# aquarium.net
KiCad netlist of a schematic drawn in EAGLE
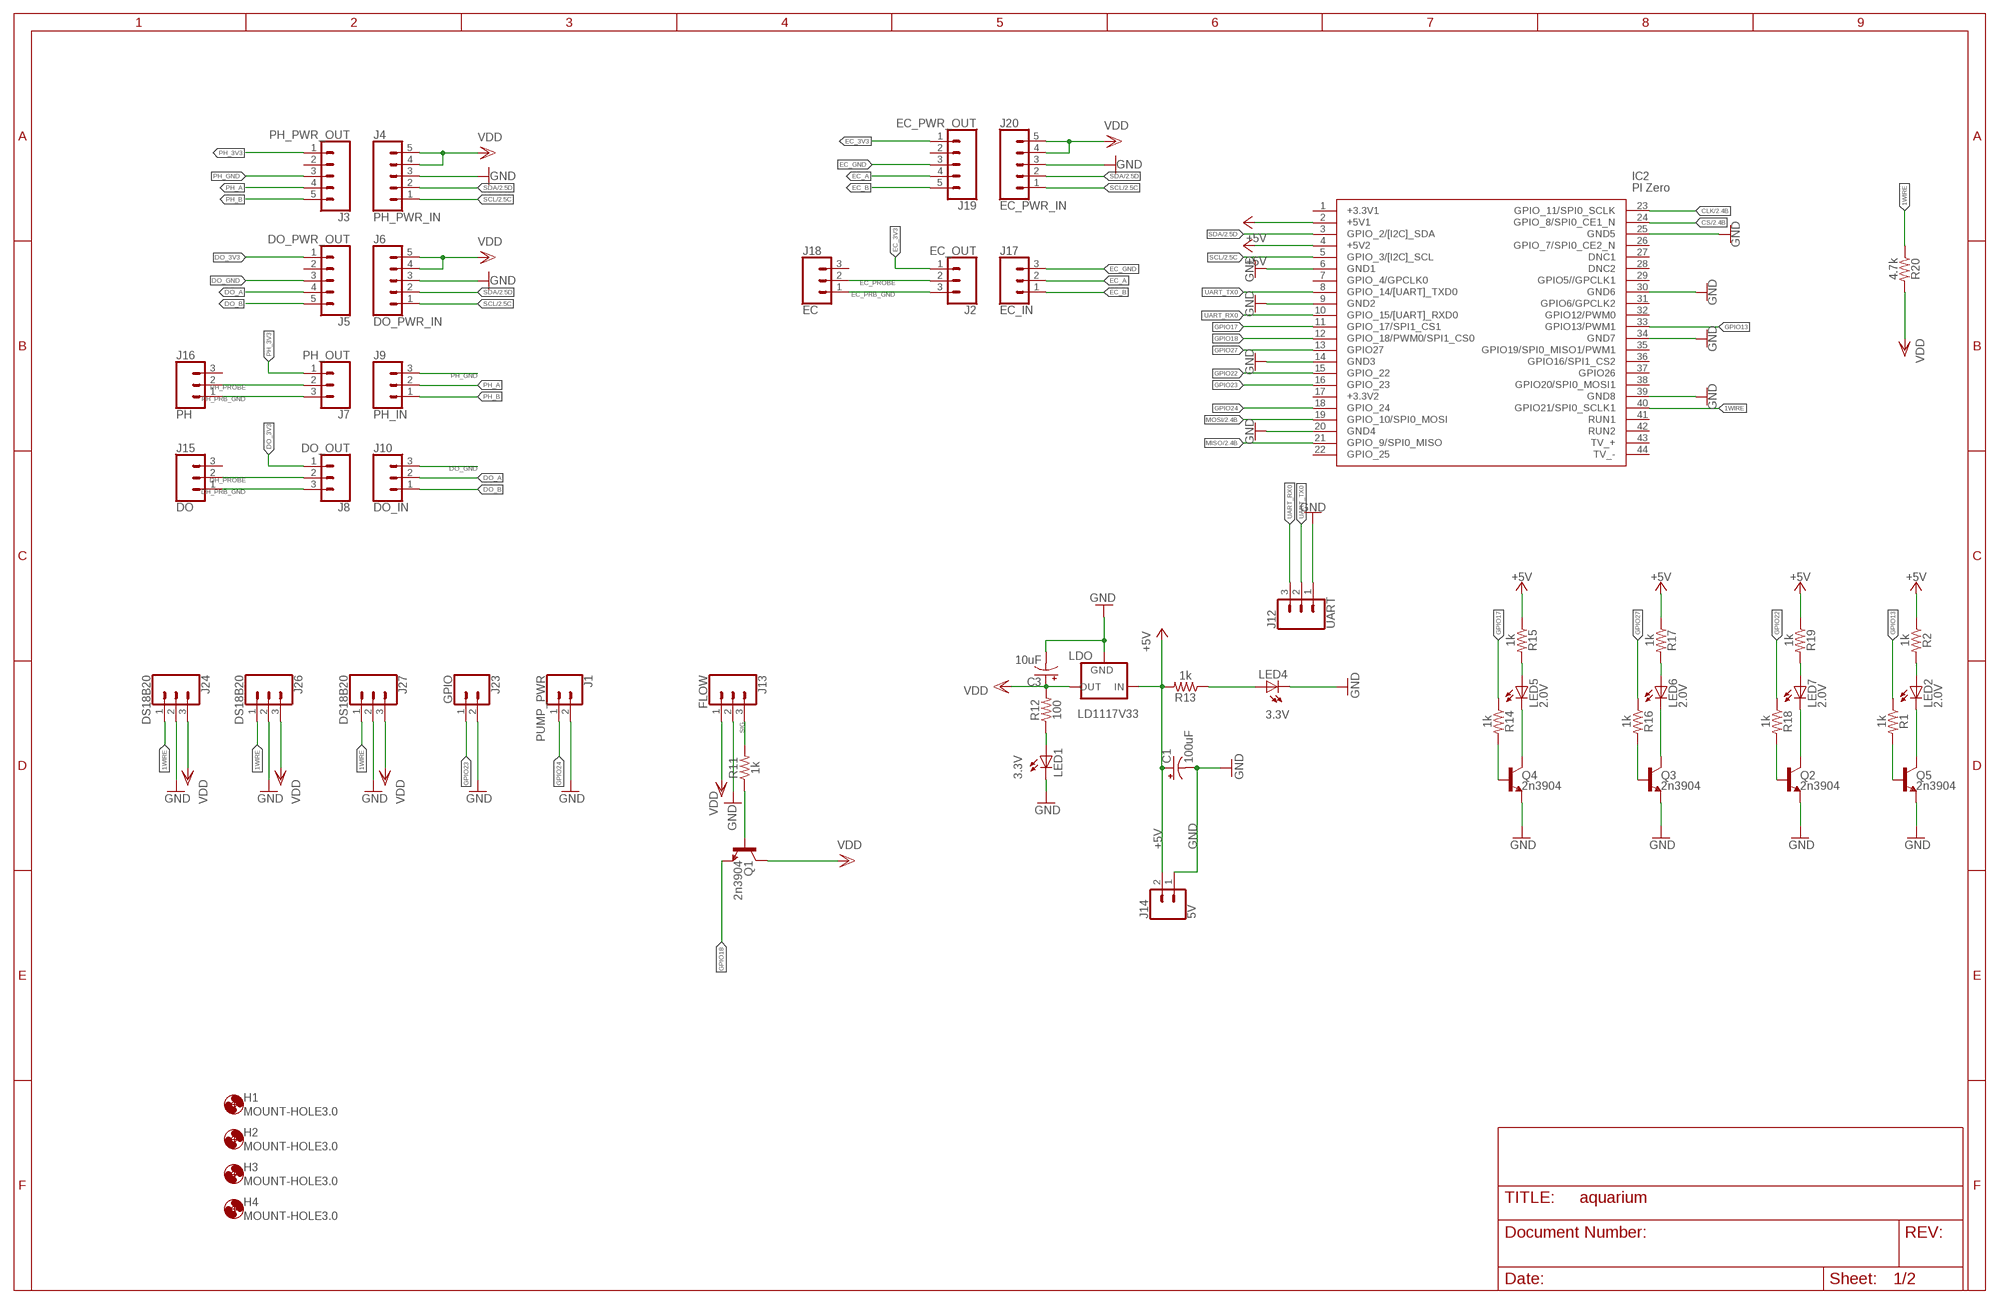
[diagram p0: schematic, sheet 1]
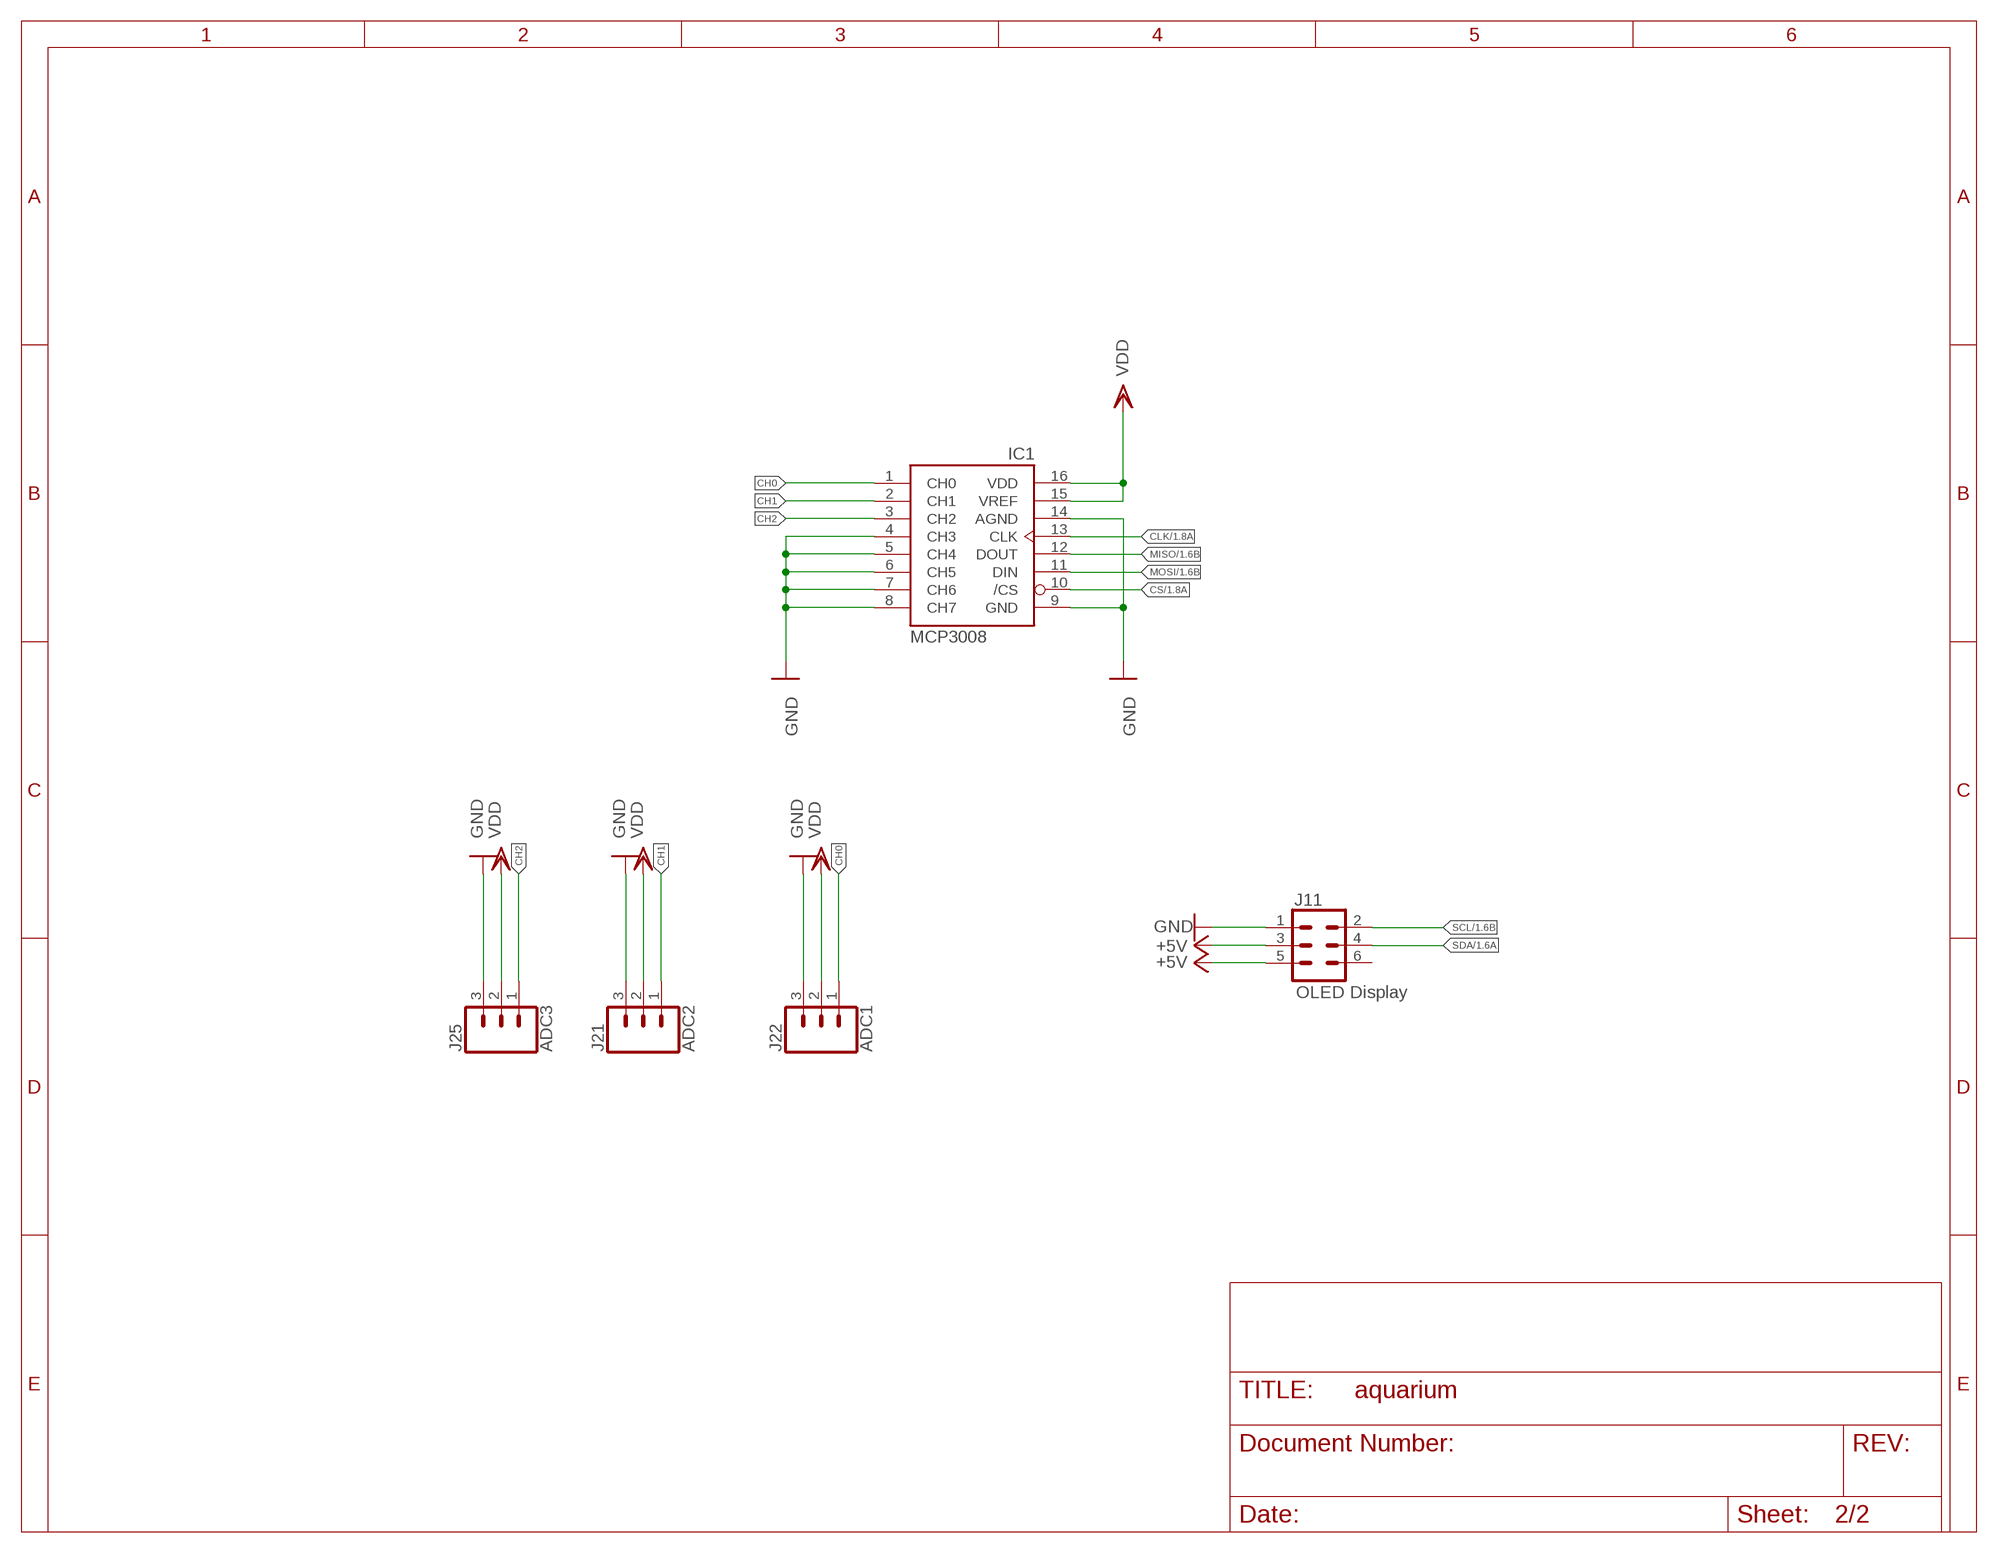
[diagram p1: schematic, sheet 2]

(export (version "E")
  (design (tool "Eeschema 10.0.6"))
  (components
    (comp (ref "C1")
      (value "100uF")
      (footprint "eagle-import:CPOL-RADIAL-2.5MM-6.5MM")
      (libsource (lib "eagle-import") (part "100UF-POLAR-RADIAL-2.5MM-25V-20%"))
    )
    (comp (ref "C3")
      (value "10uF")
      (footprint "eagle-import:CPOL-RADIAL-2.5MM-5MM")
      (libsource (lib "eagle-import") (part "10UF-POLAR-RADIAL-2.5MM-25V-20%"))
    )
    (comp (ref "H1")
      (value "MOUNT-HOLE3.0")
      (footprint "eagle-import:3,0")
      (libsource (lib "eagle-import") (part "MOUNT-HOLE3.0"))
    )
    (comp (ref "H2")
      (value "MOUNT-HOLE3.0")
      (footprint "eagle-import:3,0")
      (libsource (lib "eagle-import") (part "MOUNT-HOLE3.0"))
    )
    (comp (ref "H3")
      (value "MOUNT-HOLE3.0")
      (footprint "eagle-import:3,0")
      (libsource (lib "eagle-import") (part "MOUNT-HOLE3.0"))
    )
    (comp (ref "H4")
      (value "MOUNT-HOLE3.0")
      (footprint "eagle-import:3,0")
      (libsource (lib "eagle-import") (part "MOUNT-HOLE3.0"))
    )
    (comp (ref "IC2")
      (value "PI Zero")
      (footprint "eagle-import:RASPBERRYPIZEROWV13")
      (fields (field (name "ARROW_PART_NUMBER") "Raspberry Pi Zero W (v1.3)"))
      (libsource (lib "eagle-import") (part "RASPBERRY_PI_ZERO_W_(V1.3)"))
    )
    (comp (ref "J1")
      (value "PUMP_PWR")
      (footprint "eagle-import:1X02")
      (libsource (lib "eagle-import") (part "CONN_02"))
    )
    (comp (ref "J2")
      (value "EC_OUT")
      (footprint "eagle-import:1X03")
      (libsource (lib "eagle-import") (part "CONN_03"))
    )
    (comp (ref "J3")
      (value "PH_PWR_OUT")
      (footprint "eagle-import:1X05")
      (libsource (lib "eagle-import") (part "CONN_05"))
    )
    (comp (ref "J4")
      (value "PH_PWR_IN")
      (footprint "eagle-import:1X05")
      (libsource (lib "eagle-import") (part "CONN_05"))
    )
    (comp (ref "J5")
      (value "DO_PWR_OUT")
      (footprint "eagle-import:1X05")
      (libsource (lib "eagle-import") (part "CONN_05"))
    )
    (comp (ref "J6")
      (value "DO_PWR_IN")
      (footprint "eagle-import:1X05")
      (libsource (lib "eagle-import") (part "CONN_05"))
    )
    (comp (ref "J7")
      (value "PH_OUT")
      (footprint "eagle-import:1X03")
      (libsource (lib "eagle-import") (part "CONN_03"))
    )
    (comp (ref "J8")
      (value "DO_OUT")
      (footprint "eagle-import:1X03")
      (libsource (lib "eagle-import") (part "CONN_03"))
    )
    (comp (ref "J9")
      (value "PH_IN")
      (footprint "eagle-import:1X03")
      (libsource (lib "eagle-import") (part "CONN_03"))
    )
    (comp (ref "J10")
      (value "DO_IN")
      (footprint "eagle-import:1X03")
      (libsource (lib "eagle-import") (part "CONN_03"))
    )
    (comp (ref "J12")
      (value "UART")
      (footprint "eagle-import:1X03")
      (libsource (lib "eagle-import") (part "CONN_03"))
    )
    (comp (ref "J13")
      (value "FLOW")
      (footprint "eagle-import:1X03")
      (libsource (lib "eagle-import") (part "CONN_03"))
    )
    (comp (ref "J14")
      (value "5V")
      (footprint "eagle-import:1X02")
      (libsource (lib "eagle-import") (part "CONN_02"))
    )
    (comp (ref "J15")
      (value "DO")
      (footprint "eagle-import:1X03")
      (libsource (lib "eagle-import") (part "CONN_03"))
    )
    (comp (ref "J16")
      (value "PH")
      (footprint "eagle-import:1X03")
      (libsource (lib "eagle-import") (part "CONN_03"))
    )
    (comp (ref "J17")
      (value "EC_IN")
      (footprint "eagle-import:1X03")
      (libsource (lib "eagle-import") (part "CONN_03"))
    )
    (comp (ref "J18")
      (value "EC")
      (footprint "eagle-import:1X03")
      (libsource (lib "eagle-import") (part "CONN_03"))
    )
    (comp (ref "J19")
      (value "EC_PWR_OUT")
      (footprint "eagle-import:1X05")
      (libsource (lib "eagle-import") (part "CONN_05"))
    )
    (comp (ref "J20")
      (value "EC_PWR_IN")
      (footprint "eagle-import:1X05")
      (libsource (lib "eagle-import") (part "CONN_05"))
    )
    (comp (ref "J23")
      (value "GPIO")
      (footprint "eagle-import:1X02")
      (libsource (lib "eagle-import") (part "CONN_02"))
    )
    (comp (ref "J24")
      (value "DS18B20")
      (footprint "eagle-import:1X03")
      (libsource (lib "eagle-import") (part "CONN_03"))
    )
    (comp (ref "J26")
      (value "DS18B20")
      (footprint "eagle-import:1X03")
      (libsource (lib "eagle-import") (part "CONN_03"))
    )
    (comp (ref "J27")
      (value "DS18B20")
      (footprint "eagle-import:1X03")
      (libsource (lib "eagle-import") (part "CONN_03"))
    )
    (comp (ref "LDO")
      (value "LD1117V33")
      (footprint "eagle-import:78XXL")
      (libsource (lib "eagle-import") (part "V_REG_LD1117VXX"))
    )
    (comp (ref "LED1")
      (value "3.3V")
      (footprint "eagle-import:LED3MM")
      (libsource (lib "eagle-import") (part "LED3MM"))
    )
    (comp (ref "LED2")
      (value "2.0V")
      (footprint "eagle-import:LED3MM")
      (libsource (lib "eagle-import") (part "LED3MM"))
    )
    (comp (ref "LED4")
      (value "3.3V")
      (footprint "eagle-import:LED3MM")
      (libsource (lib "eagle-import") (part "LED3MM"))
    )
    (comp (ref "LED5")
      (value "2.0V")
      (footprint "eagle-import:LED3MM")
      (libsource (lib "eagle-import") (part "LED3MM"))
    )
    (comp (ref "LED6")
      (value "2.0V")
      (footprint "eagle-import:LED3MM")
      (libsource (lib "eagle-import") (part "LED3MM"))
    )
    (comp (ref "LED7")
      (value "2.0V")
      (footprint "eagle-import:LED3MM")
      (libsource (lib "eagle-import") (part "LED3MM"))
    )
    (comp (ref "Q1")
      (value "2n3904")
      (footprint "eagle-import:TO-92")
      (libsource (lib "eagle-import") (part "TRANS_NPN-2N3904"))
    )
    (comp (ref "Q2")
      (value "2n3904")
      (footprint "eagle-import:TO-92")
      (libsource (lib "eagle-import") (part "TRANS_NPN-2N3904"))
    )
    (comp (ref "Q3")
      (value "2n3904")
      (footprint "eagle-import:TO-92")
      (libsource (lib "eagle-import") (part "TRANS_NPN-2N3904"))
    )
    (comp (ref "Q4")
      (value "2n3904")
      (footprint "eagle-import:TO-92")
      (libsource (lib "eagle-import") (part "TRANS_NPN-2N3904"))
    )
    (comp (ref "Q5")
      (value "2n3904")
      (footprint "eagle-import:TO-92")
      (libsource (lib "eagle-import") (part "TRANS_NPN-2N3904"))
    )
    (comp (ref "R1")
      (value "1k")
      (footprint "eagle-import:AXIAL-0.3")
      (libsource (lib "eagle-import") (part "1KOHM-HORIZ-1/4W-5%"))
    )
    (comp (ref "R2")
      (value "1k")
      (footprint "eagle-import:AXIAL-0.3")
      (libsource (lib "eagle-import") (part "1KOHM-HORIZ-1/4W-5%"))
    )
    (comp (ref "R11")
      (value "1k")
      (footprint "eagle-import:AXIAL-0.3")
      (libsource (lib "eagle-import") (part "1KOHM-HORIZ-1/4W-5%"))
    )
    (comp (ref "R12")
      (value "100")
      (footprint "eagle-import:AXIAL-0.3")
      (libsource (lib "eagle-import") (part "1KOHM-HORIZ-1/4W-5%"))
    )
    (comp (ref "R13")
      (value "1k")
      (footprint "eagle-import:AXIAL-0.3")
      (libsource (lib "eagle-import") (part "1KOHM-HORIZ-1/4W-5%"))
    )
    (comp (ref "R14")
      (value "1k")
      (footprint "eagle-import:AXIAL-0.3")
      (libsource (lib "eagle-import") (part "1KOHM-HORIZ-1/4W-5%"))
    )
    (comp (ref "R15")
      (value "1k")
      (footprint "eagle-import:AXIAL-0.3")
      (libsource (lib "eagle-import") (part "1KOHM-HORIZ-1/4W-5%"))
    )
    (comp (ref "R16")
      (value "1k")
      (footprint "eagle-import:AXIAL-0.3")
      (libsource (lib "eagle-import") (part "1KOHM-HORIZ-1/4W-5%"))
    )
    (comp (ref "R17")
      (value "1k")
      (footprint "eagle-import:AXIAL-0.3")
      (libsource (lib "eagle-import") (part "1KOHM-HORIZ-1/4W-5%"))
    )
    (comp (ref "R18")
      (value "1k")
      (footprint "eagle-import:AXIAL-0.3")
      (libsource (lib "eagle-import") (part "1KOHM-HORIZ-1/4W-5%"))
    )
    (comp (ref "R19")
      (value "1k")
      (footprint "eagle-import:AXIAL-0.3")
      (libsource (lib "eagle-import") (part "1KOHM-HORIZ-1/4W-5%"))
    )
    (comp (ref "R20")
      (value "4.7k")
      (footprint "eagle-import:AXIAL-0.3")
      (libsource (lib "eagle-import") (part "1KOHM-HORIZ-1/4W-5%"))
    )
    (comp (ref "IC1")
      (value "MCP3008")
      (footprint "eagle-import:DIL16")
      (libsource (lib "eagle-import") (part "MCP3008"))
    )
    (comp (ref "J11")
      (value "OLED Display")
      (footprint "eagle-import:2X3")
      (libsource (lib "eagle-import") (part "CONN_03X2FEMALE"))
    )
    (comp (ref "J21")
      (value "ADC2")
      (footprint "eagle-import:1X03")
      (libsource (lib "eagle-import") (part "CONN_03"))
    )
    (comp (ref "J22")
      (value "ADC1")
      (footprint "eagle-import:1X03")
      (libsource (lib "eagle-import") (part "CONN_03"))
    )
    (comp (ref "J25")
      (value "ADC3")
      (footprint "eagle-import:1X03")
      (libsource (lib "eagle-import") (part "CONN_03"))
    )
  )
  (nets
    (net (code "1") (name "+5V") (class "Default")
      (node (ref "C1") (pin "1") (pinfunction "+_1") (pintype "passive"))
      (node (ref "IC2") (pin "2") (pinfunction "+5V1_2") (pintype "bidirectional"))
      (node (ref "IC2") (pin "4") (pinfunction "+5V2_4") (pintype "bidirectional"))
      (node (ref "J11") (pin "3") (pinfunction "3_3") (pintype "bidirectional"))
      (node (ref "J11") (pin "5") (pinfunction "5_5") (pintype "bidirectional"))
      (node (ref "J14") (pin "2") (pinfunction "2_2") (pintype "passive"))
      (node (ref "LDO") (pin "OUT") (pinfunction "IN_OUT") (pintype "input"))
      (node (ref "R13") (pin "P$2") (pinfunction "2_P$2") (pintype "passive"))
      (node (ref "R15") (pin "P$1") (pinfunction "1_P$1") (pintype "passive"))
      (node (ref "R17") (pin "P$1") (pinfunction "1_P$1") (pintype "passive"))
      (node (ref "R19") (pin "P$1") (pinfunction "1_P$1") (pintype "passive"))
      (node (ref "R2") (pin "P$1") (pinfunction "1_P$1") (pintype "passive"))
    )
    (net (code "2") (name "1WIRE") (class "Default")
      (node (ref "IC2") (pin "40") (pinfunction "GPIO21/SPI0_SCLK1_40") (pintype "bidirectional"))
      (node (ref "J24") (pin "1") (pinfunction "1_1") (pintype "passive"))
      (node (ref "J26") (pin "1") (pinfunction "1_1") (pintype "passive"))
      (node (ref "J27") (pin "1") (pinfunction "1_1") (pintype "passive"))
      (node (ref "R20") (pin "P$1") (pinfunction "1_P$1") (pintype "passive"))
    )
    (net (code "3") (name "CH0") (class "Default")
      (node (ref "IC1") (pin "1") (pinfunction "CH0_1") (pintype "input"))
      (node (ref "J22") (pin "1") (pinfunction "1_1") (pintype "passive"))
    )
    (net (code "4") (name "CH1") (class "Default")
      (node (ref "IC1") (pin "2") (pinfunction "CH1_2") (pintype "input"))
      (node (ref "J21") (pin "1") (pinfunction "1_1") (pintype "passive"))
    )
    (net (code "5") (name "CH2") (class "Default")
      (node (ref "IC1") (pin "3") (pinfunction "CH2_3") (pintype "input"))
      (node (ref "J25") (pin "1") (pinfunction "1_1") (pintype "passive"))
    )
    (net (code "6") (name "CLK") (class "Default")
      (node (ref "IC1") (pin "13") (pinfunction "CLK_13") (pintype "input"))
      (node (ref "IC2") (pin "23") (pinfunction "GPIO_11/SPI0_SCLK_23") (pintype "bidirectional"))
    )
    (net (code "7") (name "CS") (class "Default")
      (node (ref "IC1") (pin "10") (pinfunction "/CS_10") (pintype "input"))
      (node (ref "IC2") (pin "24") (pinfunction "GPIO_8/SPI0_CE1_N_24") (pintype "bidirectional"))
    )
    (net (code "8") (name "DH_PRB_GND") (class "Default")
      (node (ref "J15") (pin "1") (pinfunction "1_1") (pintype "passive"))
      (node (ref "J8") (pin "3") (pinfunction "3_3") (pintype "passive"))
    )
    (net (code "9") (name "DH_PROBE") (class "Default")
      (node (ref "J15") (pin "2") (pinfunction "2_2") (pintype "passive"))
      (node (ref "J8") (pin "2") (pinfunction "2_2") (pintype "passive"))
    )
    (net (code "10") (name "DO_3V3") (class "Default")
      (node (ref "J5") (pin "1") (pinfunction "1_1") (pintype "passive"))
      (node (ref "J8") (pin "1") (pinfunction "1_1") (pintype "passive"))
    )
    (net (code "11") (name "DO_A") (class "Default")
      (node (ref "J10") (pin "2") (pinfunction "2_2") (pintype "passive"))
      (node (ref "J5") (pin "4") (pinfunction "4_4") (pintype "passive"))
    )
    (net (code "12") (name "DO_B") (class "Default")
      (node (ref "J10") (pin "1") (pinfunction "1_1") (pintype "passive"))
      (node (ref "J5") (pin "5") (pinfunction "5_5") (pintype "passive"))
    )
    (net (code "13") (name "DO_GND") (class "Default")
      (node (ref "J10") (pin "3") (pinfunction "3_3") (pintype "passive"))
      (node (ref "J5") (pin "3") (pinfunction "3_3") (pintype "passive"))
    )
    (net (code "14") (name "EC_3V3") (class "Default")
      (node (ref "J19") (pin "1") (pinfunction "1_1") (pintype "passive"))
      (node (ref "J2") (pin "1") (pinfunction "1_1") (pintype "passive"))
    )
    (net (code "15") (name "EC_A") (class "Default")
      (node (ref "J17") (pin "2") (pinfunction "2_2") (pintype "passive"))
      (node (ref "J19") (pin "4") (pinfunction "4_4") (pintype "passive"))
    )
    (net (code "16") (name "EC_B") (class "Default")
      (node (ref "J17") (pin "1") (pinfunction "1_1") (pintype "passive"))
      (node (ref "J19") (pin "5") (pinfunction "5_5") (pintype "passive"))
    )
    (net (code "17") (name "EC_GND") (class "Default")
      (node (ref "J17") (pin "3") (pinfunction "3_3") (pintype "passive"))
      (node (ref "J19") (pin "3") (pinfunction "3_3") (pintype "passive"))
    )
    (net (code "18") (name "EC_PRB_GND") (class "Default")
      (node (ref "J18") (pin "1") (pinfunction "1_1") (pintype "passive"))
      (node (ref "J2") (pin "3") (pinfunction "3_3") (pintype "passive"))
    )
    (net (code "19") (name "EC_PROBE") (class "Default")
      (node (ref "J18") (pin "2") (pinfunction "2_2") (pintype "passive"))
      (node (ref "J2") (pin "2") (pinfunction "2_2") (pintype "passive"))
    )
    (net (code "20") (name "GND") (class "Default")
      (node (ref "C1") (pin "2") (pinfunction "-_2") (pintype "passive"))
      (node (ref "C3") (pin "2") (pinfunction "-_2") (pintype "passive"))
      (node (ref "IC1") (pin "14") (pinfunction "AGND_14") (pintype "power_in"))
      (node (ref "IC1") (pin "4") (pinfunction "CH3_4") (pintype "input"))
      (node (ref "IC1") (pin "5") (pinfunction "CH4_5") (pintype "input"))
      (node (ref "IC1") (pin "6") (pinfunction "CH5_6") (pintype "input"))
      (node (ref "IC1") (pin "7") (pinfunction "CH6_7") (pintype "input"))
      (node (ref "IC1") (pin "8") (pinfunction "CH7_8") (pintype "input"))
      (node (ref "IC1") (pin "9") (pinfunction "GND_9") (pintype "power_in"))
      (node (ref "IC2") (pin "14") (pinfunction "GND3_14") (pintype "bidirectional"))
      (node (ref "IC2") (pin "20") (pinfunction "GND4_20") (pintype "bidirectional"))
      (node (ref "IC2") (pin "25") (pinfunction "GND5_25") (pintype "bidirectional"))
      (node (ref "IC2") (pin "30") (pinfunction "GND6_30") (pintype "bidirectional"))
      (node (ref "IC2") (pin "34") (pinfunction "GND7_34") (pintype "bidirectional"))
      (node (ref "IC2") (pin "39") (pinfunction "GND8_39") (pintype "bidirectional"))
      (node (ref "IC2") (pin "6") (pinfunction "GND1_6") (pintype "bidirectional"))
      (node (ref "IC2") (pin "9") (pinfunction "GND2_9") (pintype "bidirectional"))
      (node (ref "J1") (pin "2") (pinfunction "2_2") (pintype "passive"))
      (node (ref "J11") (pin "1") (pinfunction "1_1") (pintype "bidirectional"))
      (node (ref "J12") (pin "1") (pinfunction "1_1") (pintype "passive"))
      (node (ref "J13") (pin "2") (pinfunction "2_2") (pintype "passive"))
      (node (ref "J14") (pin "1") (pinfunction "1_1") (pintype "passive"))
      (node (ref "J20") (pin "3") (pinfunction "3_3") (pintype "passive"))
      (node (ref "J21") (pin "3") (pinfunction "3_3") (pintype "passive"))
      (node (ref "J22") (pin "3") (pinfunction "3_3") (pintype "passive"))
      (node (ref "J23") (pin "2") (pinfunction "2_2") (pintype "passive"))
      (node (ref "J24") (pin "2") (pinfunction "2_2") (pintype "passive"))
      (node (ref "J25") (pin "3") (pinfunction "3_3") (pintype "passive"))
      (node (ref "J26") (pin "2") (pinfunction "2_2") (pintype "passive"))
      (node (ref "J27") (pin "2") (pinfunction "2_2") (pintype "passive"))
      (node (ref "J4") (pin "3") (pinfunction "3_3") (pintype "passive"))
      (node (ref "J6") (pin "3") (pinfunction "3_3") (pintype "passive"))
      (node (ref "LDO") (pin "IN") (pinfunction "GND_IN") (pintype "input"))
      (node (ref "LED1") (pin "K") (pinfunction "C_K") (pintype "passive"))
      (node (ref "LED4") (pin "K") (pinfunction "C_K") (pintype "passive"))
      (node (ref "Q2") (pin "1") (pinfunction "E_1") (pintype "passive"))
      (node (ref "Q3") (pin "1") (pinfunction "E_1") (pintype "passive"))
      (node (ref "Q4") (pin "1") (pinfunction "E_1") (pintype "passive"))
      (node (ref "Q5") (pin "1") (pinfunction "E_1") (pintype "passive"))
    )
    (net (code "21") (name "GPIO13") (class "Default")
      (node (ref "IC2") (pin "33") (pinfunction "GPIO13/PWM1_33") (pintype "bidirectional"))
      (node (ref "R1") (pin "P$1") (pinfunction "1_P$1") (pintype "passive"))
    )
    (net (code "22") (name "GPIO17") (class "Default")
      (node (ref "IC2") (pin "11") (pinfunction "GPIO_17/SPI1_CS1_11") (pintype "bidirectional"))
      (node (ref "R14") (pin "P$1") (pinfunction "1_P$1") (pintype "passive"))
    )
    (net (code "23") (name "GPIO18") (class "Default")
      (node (ref "IC2") (pin "12") (pinfunction "GPIO_18/PWM0/SPI1_CS0_12") (pintype "bidirectional"))
      (node (ref "Q1") (pin "1") (pinfunction "E_1") (pintype "passive"))
    )
    (net (code "24") (name "GPIO22") (class "Default")
      (node (ref "IC2") (pin "15") (pinfunction "GPIO_22_15") (pintype "bidirectional"))
      (node (ref "R18") (pin "P$1") (pinfunction "1_P$1") (pintype "passive"))
    )
    (net (code "25") (name "GPIO23") (class "Default")
      (node (ref "IC2") (pin "16") (pinfunction "GPIO_23_16") (pintype "bidirectional"))
      (node (ref "J23") (pin "1") (pinfunction "1_1") (pintype "passive"))
    )
    (net (code "26") (name "GPIO24") (class "Default")
      (node (ref "IC2") (pin "18") (pinfunction "GPIO_24_18") (pintype "bidirectional"))
      (node (ref "J1") (pin "1") (pinfunction "1_1") (pintype "passive"))
    )
    (net (code "27") (name "GPIO27") (class "Default")
      (node (ref "IC2") (pin "13") (pinfunction "GPIO27_13") (pintype "bidirectional"))
      (node (ref "R16") (pin "P$1") (pinfunction "1_P$1") (pintype "passive"))
    )
    (net (code "28") (name "MISO") (class "Default")
      (node (ref "IC1") (pin "12") (pinfunction "DOUT_12") (pintype "output"))
      (node (ref "IC2") (pin "21") (pinfunction "GPIO_9/SPI0_MISO_21") (pintype "bidirectional"))
    )
    (net (code "29") (name "MOSI") (class "Default")
      (node (ref "IC1") (pin "11") (pinfunction "DIN_11") (pintype "input"))
      (node (ref "IC2") (pin "19") (pinfunction "GPIO_10/SPI0_MOSI_19") (pintype "bidirectional"))
    )
    (net (code "30") (name "Net-(LED2-C)") (class "Default")
      (node (ref "LED2") (pin "K") (pinfunction "C_K") (pintype "passive"))
      (node (ref "Q5") (pin "3") (pinfunction "C_3") (pintype "passive"))
    )
    (net (code "31") (name "Net-(LED5-C)") (class "Default")
      (node (ref "LED5") (pin "K") (pinfunction "C_K") (pintype "passive"))
      (node (ref "Q4") (pin "3") (pinfunction "C_3") (pintype "passive"))
    )
    (net (code "32") (name "Net-(LED6-C)") (class "Default")
      (node (ref "LED6") (pin "K") (pinfunction "C_K") (pintype "passive"))
      (node (ref "Q3") (pin "3") (pinfunction "C_3") (pintype "passive"))
    )
    (net (code "33") (name "Net-(LED7-C)") (class "Default")
      (node (ref "LED7") (pin "K") (pinfunction "C_K") (pintype "passive"))
      (node (ref "Q2") (pin "3") (pinfunction "C_3") (pintype "passive"))
    )
    (net (code "34") (name "Net-(Q1-B)") (class "Default")
      (node (ref "Q1") (pin "2") (pinfunction "B_2") (pintype "passive"))
      (node (ref "R11") (pin "P$1") (pinfunction "1_P$1") (pintype "passive"))
    )
    (net (code "35") (name "Net-(Q2-B)") (class "Default")
      (node (ref "Q2") (pin "2") (pinfunction "B_2") (pintype "passive"))
      (node (ref "R18") (pin "P$2") (pinfunction "2_P$2") (pintype "passive"))
    )
    (net (code "36") (name "Net-(Q3-B)") (class "Default")
      (node (ref "Q3") (pin "2") (pinfunction "B_2") (pintype "passive"))
      (node (ref "R16") (pin "P$2") (pinfunction "2_P$2") (pintype "passive"))
    )
    (net (code "37") (name "Net-(Q4-B)") (class "Default")
      (node (ref "Q4") (pin "2") (pinfunction "B_2") (pintype "passive"))
      (node (ref "R14") (pin "P$2") (pinfunction "2_P$2") (pintype "passive"))
    )
    (net (code "38") (name "Net-(Q5-B)") (class "Default")
      (node (ref "Q5") (pin "2") (pinfunction "B_2") (pintype "passive"))
      (node (ref "R1") (pin "P$2") (pinfunction "2_P$2") (pintype "passive"))
    )
    (net (code "39") (name "Net-(R2-2)") (class "Default")
      (node (ref "LED2") (pin "A") (pinfunction "A_A") (pintype "passive"))
      (node (ref "R2") (pin "P$2") (pinfunction "2_P$2") (pintype "passive"))
    )
    (net (code "40") (name "Net-(R12-1)") (class "Default")
      (node (ref "LED1") (pin "A") (pinfunction "A_A") (pintype "passive"))
      (node (ref "R12") (pin "P$1") (pinfunction "1_P$1") (pintype "passive"))
    )
    (net (code "41") (name "Net-(R13-1)") (class "Default")
      (node (ref "LED4") (pin "A") (pinfunction "A_A") (pintype "passive"))
      (node (ref "R13") (pin "P$1") (pinfunction "1_P$1") (pintype "passive"))
    )
    (net (code "42") (name "Net-(R15-2)") (class "Default")
      (node (ref "LED5") (pin "A") (pinfunction "A_A") (pintype "passive"))
      (node (ref "R15") (pin "P$2") (pinfunction "2_P$2") (pintype "passive"))
    )
    (net (code "43") (name "Net-(R17-2)") (class "Default")
      (node (ref "LED6") (pin "A") (pinfunction "A_A") (pintype "passive"))
      (node (ref "R17") (pin "P$2") (pinfunction "2_P$2") (pintype "passive"))
    )
    (net (code "44") (name "Net-(R19-2)") (class "Default")
      (node (ref "LED7") (pin "A") (pinfunction "A_A") (pintype "passive"))
      (node (ref "R19") (pin "P$2") (pinfunction "2_P$2") (pintype "passive"))
    )
    (net (code "45") (name "PH_3V3") (class "Default")
      (node (ref "J3") (pin "1") (pinfunction "1_1") (pintype "passive"))
      (node (ref "J7") (pin "1") (pinfunction "1_1") (pintype "passive"))
    )
    (net (code "46") (name "PH_A") (class "Default")
      (node (ref "J3") (pin "4") (pinfunction "4_4") (pintype "passive"))
      (node (ref "J9") (pin "2") (pinfunction "2_2") (pintype "passive"))
    )
    (net (code "47") (name "PH_B") (class "Default")
      (node (ref "J3") (pin "5") (pinfunction "5_5") (pintype "passive"))
      (node (ref "J9") (pin "1") (pinfunction "1_1") (pintype "passive"))
    )
    (net (code "48") (name "PH_GND") (class "Default")
      (node (ref "J3") (pin "3") (pinfunction "3_3") (pintype "passive"))
      (node (ref "J9") (pin "3") (pinfunction "3_3") (pintype "passive"))
    )
    (net (code "49") (name "PH_PRB_GND") (class "Default")
      (node (ref "J16") (pin "1") (pinfunction "1_1") (pintype "passive"))
      (node (ref "J7") (pin "3") (pinfunction "3_3") (pintype "passive"))
    )
    (net (code "50") (name "PH_PROBE") (class "Default")
      (node (ref "J16") (pin "2") (pinfunction "2_2") (pintype "passive"))
      (node (ref "J7") (pin "2") (pinfunction "2_2") (pintype "passive"))
    )
    (net (code "51") (name "SCL") (class "Default")
      (node (ref "IC2") (pin "5") (pinfunction "GPIO_3/[I2C]_SCL_5") (pintype "bidirectional"))
      (node (ref "J11") (pin "2") (pinfunction "2_2") (pintype "bidirectional"))
      (node (ref "J20") (pin "1") (pinfunction "1_1") (pintype "passive"))
      (node (ref "J4") (pin "1") (pinfunction "1_1") (pintype "passive"))
      (node (ref "J6") (pin "1") (pinfunction "1_1") (pintype "passive"))
    )
    (net (code "52") (name "SDA") (class "Default")
      (node (ref "IC2") (pin "3") (pinfunction "GPIO_2/[I2C]_SDA_3") (pintype "bidirectional"))
      (node (ref "J11") (pin "4") (pinfunction "4_4") (pintype "bidirectional"))
      (node (ref "J20") (pin "2") (pinfunction "2_2") (pintype "passive"))
      (node (ref "J4") (pin "2") (pinfunction "2_2") (pintype "passive"))
      (node (ref "J6") (pin "2") (pinfunction "2_2") (pintype "passive"))
    )
    (net (code "53") (name "SIG") (class "Default")
      (node (ref "J13") (pin "3") (pinfunction "3_3") (pintype "passive"))
      (node (ref "R11") (pin "P$2") (pinfunction "2_P$2") (pintype "passive"))
    )
    (net (code "54") (name "UART_RX0") (class "Default")
      (node (ref "IC2") (pin "10") (pinfunction "GPIO_15/[UART]_RXD0_10") (pintype "bidirectional"))
      (node (ref "J12") (pin "3") (pinfunction "3_3") (pintype "passive"))
    )
    (net (code "55") (name "UART_TX0") (class "Default")
      (node (ref "IC2") (pin "8") (pinfunction "GPIO_14/[UART]_TXD0_8") (pintype "bidirectional"))
      (node (ref "J12") (pin "2") (pinfunction "2_2") (pintype "passive"))
    )
    (net (code "56") (name "VDD") (class "Default")
      (node (ref "C3") (pin "1") (pinfunction "+_1") (pintype "passive"))
      (node (ref "IC1") (pin "15") (pinfunction "VREF_15") (pintype "input"))
      (node (ref "IC1") (pin "16") (pinfunction "VDD_16") (pintype "power_in"))
      (node (ref "J13") (pin "1") (pinfunction "1_1") (pintype "passive"))
      (node (ref "J20") (pin "4") (pinfunction "4_4") (pintype "passive"))
      (node (ref "J20") (pin "5") (pinfunction "5_5") (pintype "passive"))
      (node (ref "J21") (pin "2") (pinfunction "2_2") (pintype "passive"))
      (node (ref "J22") (pin "2") (pinfunction "2_2") (pintype "passive"))
      (node (ref "J24") (pin "3") (pinfunction "3_3") (pintype "passive"))
      (node (ref "J25") (pin "2") (pinfunction "2_2") (pintype "passive"))
      (node (ref "J26") (pin "3") (pinfunction "3_3") (pintype "passive"))
      (node (ref "J27") (pin "3") (pinfunction "3_3") (pintype "passive"))
      (node (ref "J4") (pin "4") (pinfunction "4_4") (pintype "passive"))
      (node (ref "J4") (pin "5") (pinfunction "5_5") (pintype "passive"))
      (node (ref "J6") (pin "4") (pinfunction "4_4") (pintype "passive"))
      (node (ref "J6") (pin "5") (pinfunction "5_5") (pintype "passive"))
      (node (ref "LDO") (pin "GND") (pinfunction "OUT_GND") (pintype "passive"))
      (node (ref "Q1") (pin "3") (pinfunction "C_3") (pintype "passive"))
      (node (ref "R12") (pin "P$2") (pinfunction "2_P$2") (pintype "passive"))
      (node (ref "R20") (pin "P$2") (pinfunction "2_P$2") (pintype "passive"))
    )
    (net (code "57") (name "unconnected-(IC2-+3.3V1-Pad1)") (class "Default")
      (node (ref "IC2") (pin "1") (pinfunction "+3.3V1_1") (pintype "bidirectional"))
    )
    (net (code "58") (name "unconnected-(IC2-+3.3V2-Pad17)") (class "Default")
      (node (ref "IC2") (pin "17") (pinfunction "+3.3V2_17") (pintype "bidirectional"))
    )
    (net (code "59") (name "unconnected-(IC2-DNC1-Pad27)") (class "Default")
      (node (ref "IC2") (pin "27") (pinfunction "DNC1_27") (pintype "bidirectional"))
    )
    (net (code "60") (name "unconnected-(IC2-DNC2-Pad28)") (class "Default")
      (node (ref "IC2") (pin "28") (pinfunction "DNC2_28") (pintype "bidirectional"))
    )
    (net (code "61") (name "unconnected-(IC2-GPIO5{slash}{slash}GPCLK1-Pad29)") (class "Default")
      (node (ref "IC2") (pin "29") (pinfunction "GPIO5//GPCLK1_29") (pintype "bidirectional"))
    )
    (net (code "62") (name "unconnected-(IC2-GPIO6{slash}GPCLK2-Pad31)") (class "Default")
      (node (ref "IC2") (pin "31") (pinfunction "GPIO6/GPCLK2_31") (pintype "bidirectional"))
    )
    (net (code "63") (name "unconnected-(IC2-GPIO12{slash}PWM0-Pad32)") (class "Default")
      (node (ref "IC2") (pin "32") (pinfunction "GPIO12/PWM0_32") (pintype "bidirectional"))
    )
    (net (code "64") (name "unconnected-(IC2-GPIO16{slash}SPI1_CS2-Pad36)") (class "Default")
      (node (ref "IC2") (pin "36") (pinfunction "GPIO16/SPI1_CS2_36") (pintype "bidirectional"))
    )
    (net (code "65") (name "unconnected-(IC2-GPIO19{slash}SPI0_MISO1{slash}PWM1-Pad35)") (class "Default")
      (node (ref "IC2") (pin "35") (pinfunction "GPIO19/SPI0_MISO1/PWM1_35") (pintype "bidirectional"))
    )
    (net (code "66") (name "unconnected-(IC2-GPIO20{slash}SPI0_MOSI1-Pad38)") (class "Default")
      (node (ref "IC2") (pin "38") (pinfunction "GPIO20/SPI0_MOSI1_38") (pintype "bidirectional"))
    )
    (net (code "67") (name "unconnected-(IC2-GPIO26-Pad37)") (class "Default")
      (node (ref "IC2") (pin "37") (pinfunction "GPIO26_37") (pintype "bidirectional"))
    )
    (net (code "68") (name "unconnected-(IC2-GPIO_4{slash}GPCLK0-Pad7)") (class "Default")
      (node (ref "IC2") (pin "7") (pinfunction "GPIO_4/GPCLK0_7") (pintype "bidirectional"))
    )
    (net (code "69") (name "unconnected-(IC2-GPIO_7{slash}SPI0_CE2_N-Pad26)") (class "Default")
      (node (ref "IC2") (pin "26") (pinfunction "GPIO_7/SPI0_CE2_N_26") (pintype "bidirectional"))
    )
    (net (code "70") (name "unconnected-(IC2-GPIO_25-Pad22)") (class "Default")
      (node (ref "IC2") (pin "22") (pinfunction "GPIO_25_22") (pintype "bidirectional"))
    )
    (net (code "71") (name "unconnected-(IC2-RUN1-Pad41)") (class "Default")
      (node (ref "IC2") (pin "41") (pinfunction "RUN1_41") (pintype "bidirectional"))
    )
    (net (code "72") (name "unconnected-(IC2-RUN2-Pad42)") (class "Default")
      (node (ref "IC2") (pin "42") (pinfunction "RUN2_42") (pintype "bidirectional"))
    )
    (net (code "73") (name "unconnected-(IC2-TV_+-Pad43)") (class "Default")
      (node (ref "IC2") (pin "43") (pinfunction "TV_+_43") (pintype "bidirectional"))
    )
    (net (code "74") (name "unconnected-(IC2-TV_--Pad44)") (class "Default")
      (node (ref "IC2") (pin "44") (pinfunction "TV_-_44") (pintype "bidirectional"))
    )
    (net (code "75") (name "unconnected-(J3-Pad2)") (class "Default")
      (node (ref "J3") (pin "2") (pinfunction "2_2") (pintype "passive"))
    )
    (net (code "76") (name "unconnected-(J5-Pad2)") (class "Default")
      (node (ref "J5") (pin "2") (pinfunction "2_2") (pintype "passive"))
    )
    (net (code "77") (name "unconnected-(J11-Pad6)") (class "Default")
      (node (ref "J11") (pin "6") (pinfunction "6_6") (pintype "bidirectional"))
    )
    (net (code "78") (name "unconnected-(J15-Pad3)") (class "Default")
      (node (ref "J15") (pin "3") (pinfunction "3_3") (pintype "passive"))
    )
    (net (code "79") (name "unconnected-(J16-Pad3)") (class "Default")
      (node (ref "J16") (pin "3") (pinfunction "3_3") (pintype "passive"))
    )
    (net (code "80") (name "unconnected-(J18-Pad3)") (class "Default")
      (node (ref "J18") (pin "3") (pinfunction "3_3") (pintype "passive"))
    )
    (net (code "81") (name "unconnected-(J19-Pad2)") (class "Default")
      (node (ref "J19") (pin "2") (pinfunction "2_2") (pintype "passive"))
    )
  )
)
